# Micro.net
KiCad netlist of a schematic drawn in Altium Designer
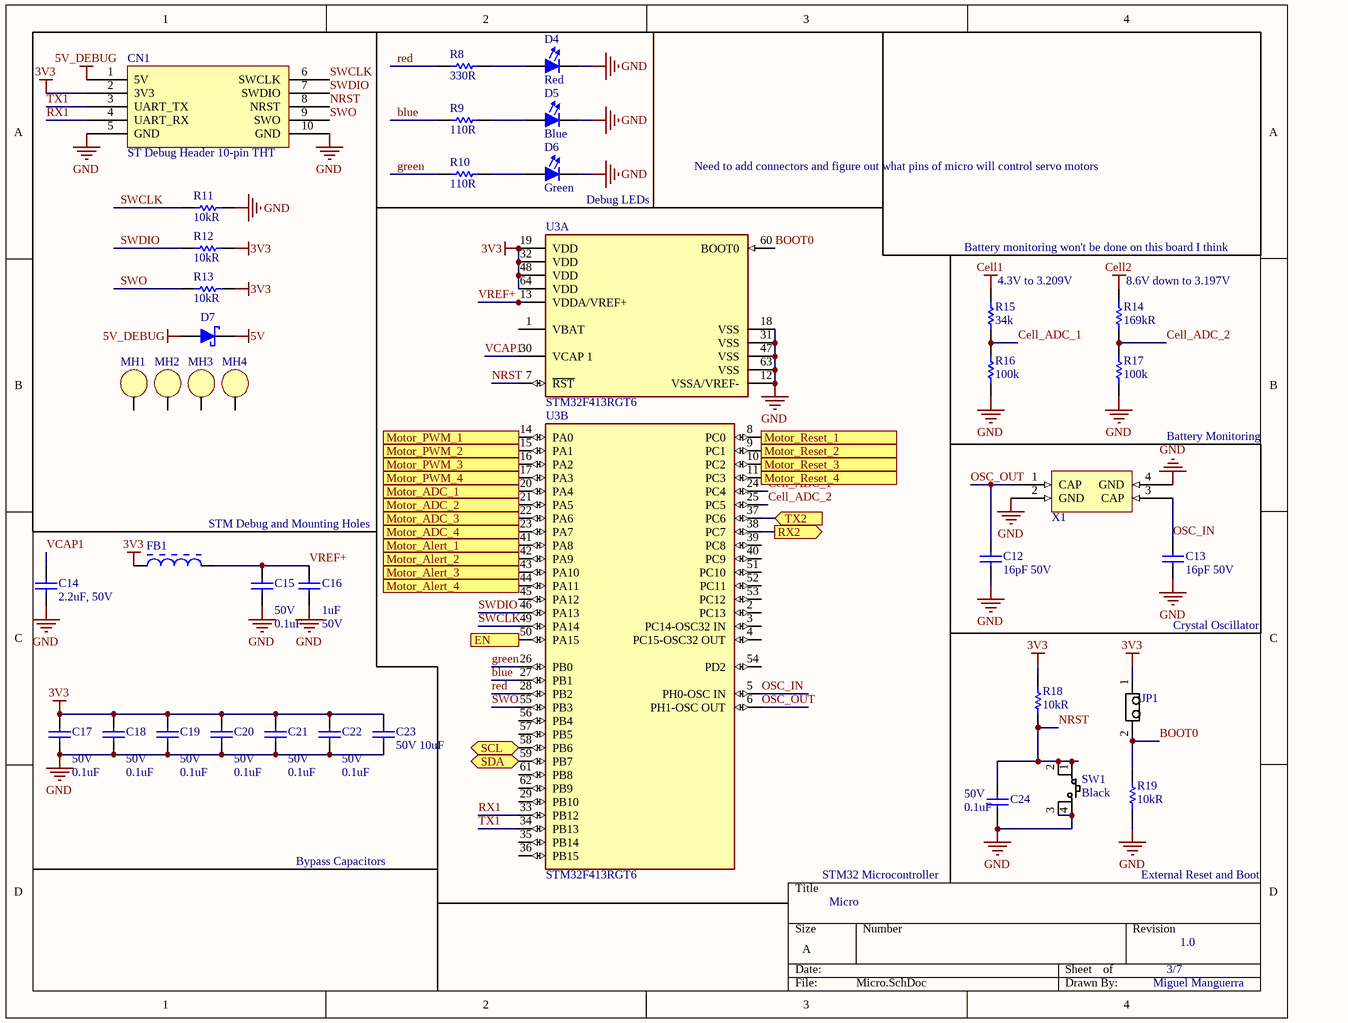
[diagram p0: Micro.SchDoc]

(export (version "E")
  (design (tool "Eeschema 10.0.6"))
  (components
    (comp (ref "C12")
      (value "16pF Ceramic 50V 5% 0603")
      (footprint "CAPC1608X90X35ML10T15")
      (description "Cap Ceramic 16pF 50V C0G 5% SMD 0603 125C Paper T/R")
      (fields (field (name "VOLTAGE") "16pF 50V") (field (name "TOLERANCE") "5%"))
      (libsource (lib "AUVIC") (part "CAP"))
    )
    (comp (ref "C13")
      (value "16pF Ceramic 50V 5% 0603")
      (footprint "CAPC1608X90X35ML10T15")
      (description "Cap Ceramic 16pF 50V C0G 5% SMD 0603 125C Paper T/R")
      (fields (field (name "VOLTAGE") "16pF 50V") (field (name "TOLERANCE") "5%"))
      (libsource (lib "AUVIC") (part "CAP"))
    )
    (comp (ref "C14")
      (value "2.2uF, 50V")
      (footprint "CAPC1608N(0603\")")
      (description "Capacitor, Ceramic, 50V, 10%, 0603 SMD, X5R")
      (fields (field (name "MADE BY") "*") (field (name "PUBLISHER") "AUVic"))
      (libsource (lib "") (part "Symbol_2"))
    )
    (comp (ref "C15")
      (value "CL10B104JB8NNNC")
      (footprint "FP-CL10-0_1-MFG")
      (description "CAP CER 0.1UF 50V X7R 0603")
      (fields
        (field (name "TOLERANCE") "5%")
        (field (name "VOLTAGE") "50V")
        (field (name "CAPACITANCE") "0.1uF")
      )
      (libsource (lib "AUVIC") (part "CAP-NP-2"))
    )
    (comp (ref "C16")
      (value "CL21B105KBFNNNG")
      (footprint "0803 CAP")
      (description "SAMSUNG ELECTRO-MECHANICS - CL21B105KBFNNNG - MLCC CAPACITORS")
      (fields
        (field (name "TOLERANCE") "10%")
        (field (name "CAPACITANCE") "1uF")
        (field (name "VOLTAGE") "50V")
      )
      (libsource (lib "") (part "Symbol_5"))
    )
    (comp (ref "C17")
      (value "CL10B104JB8NNNC")
      (footprint "FP-CL10-0_1-MFG")
      (description "CAP CER 0.1UF 50V X7R 0603")
      (fields
        (field (name "TOLERANCE") "5%")
        (field (name "VOLTAGE") "50V")
        (field (name "CAPACITANCE") "0.1uF")
      )
      (libsource (lib "AUVIC") (part "CAP-NP-2"))
    )
    (comp (ref "C18")
      (value "CL10B104JB8NNNC")
      (footprint "FP-CL10-0_1-MFG")
      (description "CAP CER 0.1UF 50V X7R 0603")
      (fields
        (field (name "TOLERANCE") "5%")
        (field (name "VOLTAGE") "50V")
        (field (name "CAPACITANCE") "0.1uF")
      )
      (libsource (lib "AUVIC") (part "CAP-NP-2"))
    )
    (comp (ref "C19")
      (value "CL10B104JB8NNNC")
      (footprint "FP-CL10-0_1-MFG")
      (description "CAP CER 0.1UF 50V X7R 0603")
      (fields
        (field (name "TOLERANCE") "5%")
        (field (name "VOLTAGE") "50V")
        (field (name "CAPACITANCE") "0.1uF")
      )
      (libsource (lib "AUVIC") (part "CAP-NP-2"))
    )
    (comp (ref "C20")
      (value "CL10B104JB8NNNC")
      (footprint "FP-CL10-0_1-MFG")
      (description "CAP CER 0.1UF 50V X7R 0603")
      (fields
        (field (name "TOLERANCE") "5%")
        (field (name "VOLTAGE") "50V")
        (field (name "CAPACITANCE") "0.1uF")
      )
      (libsource (lib "AUVIC") (part "CAP-NP-2"))
    )
    (comp (ref "C21")
      (value "CL10B104JB8NNNC")
      (footprint "FP-CL10-0_1-MFG")
      (description "CAP CER 0.1UF 50V X7R 0603")
      (fields
        (field (name "TOLERANCE") "5%")
        (field (name "VOLTAGE") "50V")
        (field (name "CAPACITANCE") "0.1uF")
      )
      (libsource (lib "AUVIC") (part "CAP-NP-2"))
    )
    (comp (ref "C22")
      (value "CL10B104JB8NNNC")
      (footprint "FP-CL10-0_1-MFG")
      (description "CAP CER 0.1UF 50V X7R 0603")
      (fields
        (field (name "TOLERANCE") "5%")
        (field (name "VOLTAGE") "50V")
        (field (name "CAPACITANCE") "0.1uF")
      )
      (libsource (lib "AUVIC") (part "CAP-NP-2"))
    )
    (comp (ref "C23")
      (value "50V 10uF")
      (footprint "CAPC3216X180X50LL20T30")
      (description "Cap Ceramic 10uF 50V X7R 10% Pad SMD 1206 125°C T/R")
      (fields (field (name "TOLERANCE") "10%"))
      (libsource (lib "AUVIC") (part "CAP-NP-2"))
    )
    (comp (ref "C24")
      (value "CL10B104JB8NNNC")
      (footprint "FP-CL10-0_1-MFG")
      (description "CAP CER 0.1UF 50V X7R 0603")
      (fields
        (field (name "TOLERANCE") "5%")
        (field (name "VOLTAGE") "50V")
        (field (name "CAPACITANCE") "0.1uF")
      )
      (libsource (lib "AUVIC") (part "CAP-NP-2"))
    )
    (comp (ref "CN1")
      (value "ST Debug Header 10-pin THT")
      (footprint "10-pin shrouded header THT")
      (description "CONN HEADER VERT 10POS 2.54MM")
      (libsource (lib "AUVIC") (part "ST Debug Header 10-pin"))
    )
    (comp (ref "D4")
      (value "Red")
      (footprint "FP-LB_Q39E-MFG")
      (description "LED Red 645nm 2-Pin Chip 0603(1608Metric) T/R")
      (libsource (lib "") (part "Symbol_1"))
    )
    (comp (ref "D5")
      (value "Blue")
      (footprint "FP-LB_Q39E-MFG")
      (description "LED BLUE DIFFUSED 0603 SMD")
      (libsource (lib "") (part "Symbol_1"))
    )
    (comp (ref "D6")
      (value "Green")
      (footprint "FP-LB_Q39E-MFG")
      (description "LED GREEN DIFFUSED 0603 SMD")
      (libsource (lib "") (part "Symbol_1"))
    )
    (comp (ref "D7")
      (value "CUS08F30,H3F")
      (footprint "SC-76")
      (description "Diode Schottky 30V 800mA Surface Mount USC")
      (libsource (lib "") (part "Symbol_4"))
    )
    (comp (ref "FB1")
      (value "BLM18AG601SN1D")
      (footprint "MURA-BLM18-F-H1-CHIP-2_V")
      (fields (field (name "TOLERANCE") "25%"))
      (libsource (lib "AUVIC") (part "MURA-FB-2"))
    )
    (comp (ref "JP1")
      (value "1x2 Male Header")
      (footprint "2X1 Males Header")
      (fields (field (name "MADE BY") "Andy Bates"))
      (libsource (lib "AUVIC") (part "1x2 Male Header"))
    )
    (comp (ref "MH1")
      (value "Mount_Hole_3mm")
      (footprint "Mount-Hole_3mm")
      (description "Mounting hold for M3 hex standoff")
      (libsource (lib "AUVIC") (part "Mount_Hole_3mm"))
    )
    (comp (ref "MH2")
      (value "Mount_Hole_3mm")
      (footprint "Mount-Hole_3mm")
      (description "Mounting hold for M3 hex standoff")
      (libsource (lib "AUVIC") (part "Mount_Hole_3mm"))
    )
    (comp (ref "MH3")
      (value "Mount_Hole_3mm")
      (footprint "Mount-Hole_3mm")
      (description "Mounting hold for M3 hex standoff")
      (libsource (lib "AUVIC") (part "Mount_Hole_3mm"))
    )
    (comp (ref "MH4")
      (value "Mount_Hole_3mm")
      (footprint "Mount-Hole_3mm")
      (description "Mounting hold for M3 hex standoff")
      (libsource (lib "AUVIC") (part "Mount_Hole_3mm"))
    )
    (comp (ref "R8")
      (value "CRCW0603330RFKEA")
      (footprint "FP-CRCW0603-e3-IPC_C")
      (description "Res Thick Film 0603 330 Ohm 1% 0.1W(1/10W) +/-100ppm/ßC Pad SMD Automotive T/R")
      (fields (field (name "TOLERANCE") "1%") (field (name "RESISTANCE") "330R"))
      (libsource (lib "AUVIC") (part "RES"))
    )
    (comp (ref "R9")
      (value "RC0603FR-07110RL")
      (footprint "RESC1608X55X25ML10T15")
      (description "RES SMD 110 OHM 1% 1/10W 0603")
      (fields (field (name "TOLERANCE") "1%") (field (name "RESISTANCE") "110R"))
      (libsource (lib "AUVIC") (part "RES"))
    )
    (comp (ref "R10")
      (value "RC0603FR-07110RL")
      (footprint "RESC1608X55X25ML10T15")
      (description "RES SMD 110 OHM 1% 1/10W 0603")
      (fields (field (name "TOLERANCE") "1%") (field (name "RESISTANCE") "110R"))
      (libsource (lib "AUVIC") (part "RES"))
    )
    (comp (ref "R11")
      (value "10kR")
      (footprint "RESC1608N(0603\")")
      (description "10kR, 1%, 1/10W, 0603 SMD")
      (fields (field (name "MADE BY") "Ashwin Sira"))
      (libsource (lib "AUVIC") (part "Symbol"))
    )
    (comp (ref "R12")
      (value "10kR")
      (footprint "RESC1608N(0603\")")
      (description "10kR, 1%, 1/10W, 0603 SMD")
      (fields (field (name "MADE BY") "Ashwin Sira"))
      (libsource (lib "AUVIC") (part "Symbol"))
    )
    (comp (ref "R13")
      (value "10kR")
      (footprint "RESC1608N(0603\")")
      (description "10kR, 1%, 1/10W, 0603 SMD")
      (fields (field (name "MADE BY") "Ashwin Sira"))
      (libsource (lib "AUVIC") (part "Symbol"))
    )
    (comp (ref "R14")
      (value "169kR, 1%, 1/10W, 0603")
      (footprint "RESC0603(1608)_M")
      (description "RES 169K OHM 1% 1/10W 0603")
      (fields (field (name "RESISTANCE") "169kR") (field (name "TOLERANCE") "1%"))
      (libsource (lib "AUVIC") (part "RES"))
    )
    (comp (ref "R15")
      (value "34kR, 1%, 1/10W, 0603")
      (footprint "RESC1608N(0603\")")
      (description "RES 34K OHM 1/10W 1% 0603 SMD")
      (fields
        (field (name "RESISTANCE") "34k")
        (field (name "MANUFACTURER PART NUMBER") "RC0603FR-0734KL")
        (field (name "MANUFACTURER") "Yageo")
      )
      (libsource (lib "AUVIC") (part "34kR, 1%, 1/10W, 0603"))
    )
    (comp (ref "R16")
      (value "100k")
      (footprint "RESC1608N(0603\")")
      (description "100kR, 1%, 1/10W, 0603 SMD")
      (fields (field (name "MADE BY") "Andy Bates"))
      (libsource (lib "AUVIC") (part "Symbol"))
    )
    (comp (ref "R17")
      (value "100k")
      (footprint "RESC1608N(0603\")")
      (description "100kR, 1%, 1/10W, 0603 SMD")
      (fields (field (name "MADE BY") "Andy Bates"))
      (libsource (lib "AUVIC") (part "Symbol"))
    )
    (comp (ref "R18")
      (value "10kR")
      (footprint "RESC1608N(0603\")")
      (description "10kR, 1%, 1/10W, 0603 SMD")
      (fields (field (name "MADE BY") "Ashwin Sira"))
      (libsource (lib "AUVIC") (part "Symbol"))
    )
    (comp (ref "R19")
      (value "10kR")
      (footprint "RESC1608N(0603\")")
      (description "10kR, 1%, 1/10W, 0603 SMD")
      (fields (field (name "MADE BY") "Ashwin Sira"))
      (libsource (lib "AUVIC") (part "Symbol"))
    )
    (comp (ref "SW1")
      (value "PTS645SL43SMTR92LFS")
      (footprint "4-SPST-NO")
      (description "Black Switch Tactile N.O. SPST Round Button Gull Wing 0.05A 12VDC 100000Cycles 1.27N SMD T/R")
      (fields (field (name "BUTTON COLOUR") "Black"))
      (libsource (lib "") (part "Symbol_3"))
    )
    (comp (ref "U3")
      (value "STM32F413RGT6")
      (footprint "FP-LQFP64-5W-MFG")
      (description "STMICROELECTRONICS - STM32F413RGT6 - MCU, ARM CORTEX-M4, 100MHZ, LQFP-64")
      (libsource (lib "AUVIC") (part "7f3deadac312a1e532344b4e443717e"))
    )
    (comp (ref "X1")
      (value "CRYSTAL 8.0MHZ 16PF SMD")
      (footprint "QFN250P750X520X140_HS-5M")
      (description "8MHz ±30ppm Crystal 16pF 80 Ohms 4-SMD, No Lead")
      (libsource (lib "AUVIC") (part "LFXTAL026380REEL"))
    )
  )
  (nets
    (net (code "1") (name "/BOOT0") (class "Default")
      (node (ref "JP1") (pin "2") (pinfunction "2_2") (pintype "passive"))
      (node (ref "R19") (pin "1") (pinfunction "1_1") (pintype "passive"))
      (node (ref "U3") (pin "60") (pinfunction "BOOT0_60") (pintype "input"))
    )
    (net (code "2") (name "/Cell_ADC_1") (class "Default")
      (node (ref "R15") (pin "1") (pinfunction "1_1") (pintype "passive"))
      (node (ref "R16") (pin "2") (pinfunction "2_2") (pintype "passive"))
      (node (ref "U3") (pin "24") (pinfunction "PC4_24") (pintype "bidirectional"))
    )
    (net (code "3") (name "/Cell_ADC_2") (class "Default")
      (node (ref "R14") (pin "1") (pinfunction "1_1") (pintype "passive"))
      (node (ref "R17") (pin "2") (pinfunction "2_2") (pintype "passive"))
      (node (ref "U3") (pin "25") (pinfunction "PC5_25") (pintype "bidirectional"))
    )
    (net (code "4") (name "/EN") (class "Default")
      (node (ref "U3") (pin "50") (pinfunction "PA15_50") (pintype "bidirectional"))
    )
    (net (code "5") (name "/Motor_ADC_1") (class "Default")
      (node (ref "U3") (pin "20") (pinfunction "PA4_20") (pintype "bidirectional"))
    )
    (net (code "6") (name "/Motor_ADC_2") (class "Default")
      (node (ref "U3") (pin "21") (pinfunction "PA5_21") (pintype "bidirectional"))
    )
    (net (code "7") (name "/Motor_ADC_3") (class "Default")
      (node (ref "U3") (pin "22") (pinfunction "PA6_22") (pintype "bidirectional"))
    )
    (net (code "8") (name "/Motor_ADC_4") (class "Default")
      (node (ref "U3") (pin "23") (pinfunction "PA7_23") (pintype "bidirectional"))
    )
    (net (code "9") (name "/Motor_Alert_1") (class "Default")
      (node (ref "U3") (pin "41") (pinfunction "PA8_41") (pintype "bidirectional"))
    )
    (net (code "10") (name "/Motor_Alert_2") (class "Default")
      (node (ref "U3") (pin "42") (pinfunction "PA9_42") (pintype "bidirectional"))
    )
    (net (code "11") (name "/Motor_Alert_3") (class "Default")
      (node (ref "U3") (pin "43") (pinfunction "PA10_43") (pintype "bidirectional"))
    )
    (net (code "12") (name "/Motor_Alert_4") (class "Default")
      (node (ref "U3") (pin "44") (pinfunction "PA11_44") (pintype "bidirectional"))
    )
    (net (code "13") (name "/Motor_PWM_1") (class "Default")
      (node (ref "U3") (pin "14") (pinfunction "PA0_14") (pintype "bidirectional"))
    )
    (net (code "14") (name "/Motor_PWM_2") (class "Default")
      (node (ref "U3") (pin "15") (pinfunction "PA1_15") (pintype "bidirectional"))
    )
    (net (code "15") (name "/Motor_PWM_3") (class "Default")
      (node (ref "U3") (pin "16") (pinfunction "PA2_16") (pintype "bidirectional"))
    )
    (net (code "16") (name "/Motor_PWM_4") (class "Default")
      (node (ref "U3") (pin "17") (pinfunction "PA3_17") (pintype "bidirectional"))
    )
    (net (code "17") (name "/Motor_Reset_1") (class "Default")
      (node (ref "U3") (pin "8") (pinfunction "PC0_8") (pintype "bidirectional"))
    )
    (net (code "18") (name "/Motor_Reset_2") (class "Default")
      (node (ref "U3") (pin "9") (pinfunction "PC1_9") (pintype "bidirectional"))
    )
    (net (code "19") (name "/Motor_Reset_3") (class "Default")
      (node (ref "U3") (pin "10") (pinfunction "PC2_10") (pintype "bidirectional"))
    )
    (net (code "20") (name "/Motor_Reset_4") (class "Default")
      (node (ref "U3") (pin "11") (pinfunction "PC3_11") (pintype "bidirectional"))
    )
    (net (code "21") (name "/NRST") (class "Default")
      (node (ref "C24") (pin "1") (pinfunction "1_1") (pintype "passive"))
      (node (ref "CN1") (pin "8") (pinfunction "NRST_8") (pintype "passive"))
      (node (ref "R18") (pin "2") (pinfunction "2_2") (pintype "passive"))
      (node (ref "SW1") (pin "1") (pinfunction "1_1") (pintype "passive"))
      (node (ref "SW1") (pin "2") (pinfunction "2_2") (pintype "passive"))
      (node (ref "U3") (pin "7") (pinfunction "~{RST}_7") (pintype "bidirectional"))
    )
    (net (code "22") (name "/OSC_IN") (class "Default")
      (node (ref "C13") (pin "2") (pinfunction "2_2") (pintype "passive"))
      (node (ref "U3") (pin "5") (pinfunction "PH0-OSC_IN_5") (pintype "bidirectional"))
      (node (ref "X1") (pin "3") (pinfunction "CAP_3") (pintype "input"))
    )
    (net (code "23") (name "/OSC_OUT") (class "Default")
      (node (ref "C12") (pin "2") (pinfunction "2_2") (pintype "passive"))
      (node (ref "U3") (pin "6") (pinfunction "PH1-OSC_OUT_6") (pintype "bidirectional"))
      (node (ref "X1") (pin "1") (pinfunction "CAP_1") (pintype "input"))
    )
    (net (code "24") (name "/RX1") (class "Default")
      (node (ref "CN1") (pin "4") (pinfunction "UART_RX_4") (pintype "passive"))
      (node (ref "U3") (pin "33") (pinfunction "PB12_33") (pintype "bidirectional"))
    )
    (net (code "25") (name "/RX2") (class "Default")
      (node (ref "U3") (pin "38") (pinfunction "PC7_38") (pintype "bidirectional"))
    )
    (net (code "26") (name "/SCL") (class "Default")
      (node (ref "U3") (pin "58") (pinfunction "PB6_58") (pintype "bidirectional"))
    )
    (net (code "27") (name "/SDA") (class "Default")
      (node (ref "U3") (pin "59") (pinfunction "PB7_59") (pintype "bidirectional"))
    )
    (net (code "28") (name "/SWCLK") (class "Default")
      (node (ref "CN1") (pin "6") (pinfunction "SWCLK_6") (pintype "passive"))
      (node (ref "R11") (pin "2") (pinfunction "2_2") (pintype "passive"))
      (node (ref "U3") (pin "49") (pinfunction "PA14_49") (pintype "bidirectional"))
    )
    (net (code "29") (name "/SWDIO") (class "Default")
      (node (ref "CN1") (pin "7") (pinfunction "SWDIO_7") (pintype "passive"))
      (node (ref "R12") (pin "2") (pinfunction "2_2") (pintype "passive"))
      (node (ref "U3") (pin "46") (pinfunction "PA13_46") (pintype "bidirectional"))
    )
    (net (code "30") (name "/SWO") (class "Default")
      (node (ref "CN1") (pin "9") (pinfunction "SWO_9") (pintype "passive"))
      (node (ref "R13") (pin "2") (pinfunction "2_2") (pintype "passive"))
      (node (ref "U3") (pin "55") (pinfunction "PB3_55") (pintype "bidirectional"))
    )
    (net (code "31") (name "/TX1") (class "Default")
      (node (ref "CN1") (pin "3") (pinfunction "UART_TX_3") (pintype "passive"))
      (node (ref "U3") (pin "34") (pinfunction "PB13_34") (pintype "bidirectional"))
    )
    (net (code "32") (name "/TX2") (class "Default")
      (node (ref "U3") (pin "37") (pinfunction "PC6_37") (pintype "bidirectional"))
    )
    (net (code "33") (name "/VCAP1") (class "Default")
      (node (ref "C14") (pin "1") (pinfunction "Anode_1") (pintype "passive"))
      (node (ref "U3") (pin "30") (pinfunction "VCAP_1_30") (pintype "power_in"))
    )
    (net (code "34") (name "/VREF+") (class "Default")
      (node (ref "C15") (pin "1") (pinfunction "1_1") (pintype "passive"))
      (node (ref "C16") (pin "1") (pinfunction "1_1") (pintype "passive"))
      (node (ref "FB1") (pin "2") (pinfunction "2_2") (pintype "passive"))
      (node (ref "U3") (pin "13") (pinfunction "VDDA/VREF+_13") (pintype "power_in"))
    )
    (net (code "35") (name "/blue") (class "Default")
      (node (ref "R9") (pin "1") (pinfunction "1_1") (pintype "passive"))
      (node (ref "U3") (pin "27") (pinfunction "PB1_27") (pintype "bidirectional"))
    )
    (net (code "36") (name "/green") (class "Default")
      (node (ref "R10") (pin "1") (pinfunction "1_1") (pintype "passive"))
      (node (ref "U3") (pin "26") (pinfunction "PB0_26") (pintype "bidirectional"))
    )
    (net (code "37") (name "/red") (class "Default")
      (node (ref "R8") (pin "1") (pinfunction "1_1") (pintype "passive"))
      (node (ref "U3") (pin "28") (pinfunction "PB2_28") (pintype "bidirectional"))
    )
    (net (code "38") (name "3V3") (class "Default")
      (node (ref "C17") (pin "1") (pinfunction "1_1") (pintype "passive"))
      (node (ref "C18") (pin "1") (pinfunction "1_1") (pintype "passive"))
      (node (ref "C19") (pin "1") (pinfunction "1_1") (pintype "passive"))
      (node (ref "C20") (pin "1") (pinfunction "1_1") (pintype "passive"))
      (node (ref "C21") (pin "1") (pinfunction "1_1") (pintype "passive"))
      (node (ref "C22") (pin "1") (pinfunction "1_1") (pintype "passive"))
      (node (ref "C23") (pin "1") (pinfunction "1_1") (pintype "passive"))
      (node (ref "CN1") (pin "2") (pinfunction "3V3_2") (pintype "passive"))
      (node (ref "FB1") (pin "1") (pinfunction "1_1") (pintype "passive"))
      (node (ref "JP1") (pin "1") (pinfunction "1_1") (pintype "passive"))
      (node (ref "R12") (pin "1") (pinfunction "1_1") (pintype "passive"))
      (node (ref "R13") (pin "1") (pinfunction "1_1") (pintype "passive"))
      (node (ref "R18") (pin "1") (pinfunction "1_1") (pintype "passive"))
      (node (ref "U3") (pin "19") (pinfunction "VDD_19") (pintype "power_in"))
      (node (ref "U3") (pin "32") (pinfunction "VDD_32") (pintype "power_in"))
      (node (ref "U3") (pin "48") (pinfunction "VDD_48") (pintype "power_in"))
      (node (ref "U3") (pin "64") (pinfunction "VDD_64") (pintype "power_in"))
    )
    (net (code "39") (name "5V") (class "Default")
      (node (ref "D7") (pin "K") (pinfunction "Cathode_K") (pintype "passive"))
    )
    (net (code "40") (name "5V_DEBUG") (class "Default")
      (node (ref "CN1") (pin "1") (pinfunction "5V_1") (pintype "passive"))
      (node (ref "D7") (pin "A") (pinfunction "Anode_A") (pintype "passive"))
    )
    (net (code "41") (name "Cell1") (class "Default")
      (node (ref "R15") (pin "2") (pinfunction "2_2") (pintype "passive"))
    )
    (net (code "42") (name "Cell2") (class "Default")
      (node (ref "R14") (pin "2") (pinfunction "2_2") (pintype "passive"))
    )
    (net (code "43") (name "GND") (class "Default")
      (node (ref "C12") (pin "1") (pinfunction "1_1") (pintype "passive"))
      (node (ref "C13") (pin "1") (pinfunction "1_1") (pintype "passive"))
      (node (ref "C14") (pin "2") (pinfunction "Cathode_2") (pintype "passive"))
      (node (ref "C15") (pin "2") (pinfunction "2_2") (pintype "passive"))
      (node (ref "C16") (pin "2") (pinfunction "2_2") (pintype "passive"))
      (node (ref "C17") (pin "2") (pinfunction "2_2") (pintype "passive"))
      (node (ref "C18") (pin "2") (pinfunction "2_2") (pintype "passive"))
      (node (ref "C19") (pin "2") (pinfunction "2_2") (pintype "passive"))
      (node (ref "C20") (pin "2") (pinfunction "2_2") (pintype "passive"))
      (node (ref "C21") (pin "2") (pinfunction "2_2") (pintype "passive"))
      (node (ref "C22") (pin "2") (pinfunction "2_2") (pintype "passive"))
      (node (ref "C23") (pin "2") (pinfunction "2_2") (pintype "passive"))
      (node (ref "C24") (pin "2") (pinfunction "2_2") (pintype "passive"))
      (node (ref "CN1") (pin "10") (pinfunction "GND_10") (pintype "passive"))
      (node (ref "CN1") (pin "5") (pinfunction "GND_5") (pintype "passive"))
      (node (ref "D4") (pin "1") (pinfunction "Cathode_1") (pintype "passive"))
      (node (ref "D5") (pin "1") (pinfunction "Cathode_1") (pintype "passive"))
      (node (ref "D6") (pin "1") (pinfunction "Cathode_1") (pintype "passive"))
      (node (ref "R11") (pin "1") (pinfunction "1_1") (pintype "passive"))
      (node (ref "R16") (pin "1") (pinfunction "1_1") (pintype "passive"))
      (node (ref "R17") (pin "1") (pinfunction "1_1") (pintype "passive"))
      (node (ref "R19") (pin "2") (pinfunction "2_2") (pintype "passive"))
      (node (ref "SW1") (pin "3") (pinfunction "3_3") (pintype "passive"))
      (node (ref "SW1") (pin "4") (pinfunction "4_4") (pintype "passive"))
      (node (ref "U3") (pin "12") (pinfunction "VSSA/VREF-_12") (pintype "power_in"))
      (node (ref "U3") (pin "18") (pinfunction "VSS_18") (pintype "power_in"))
      (node (ref "U3") (pin "31") (pinfunction "VSS_31") (pintype "power_in"))
      (node (ref "U3") (pin "47") (pinfunction "VSS_47") (pintype "power_in"))
      (node (ref "U3") (pin "63") (pinfunction "VSS_63") (pintype "power_in"))
      (node (ref "X1") (pin "2") (pinfunction "GND_2") (pintype "input"))
      (node (ref "X1") (pin "4") (pinfunction "GND_4") (pintype "input"))
    )
    (net (code "44") (name "Net-(D4-Anode)") (class "Default")
      (node (ref "D4") (pin "2") (pinfunction "Anode_2") (pintype "passive"))
      (node (ref "R8") (pin "2") (pinfunction "2_2") (pintype "passive"))
    )
    (net (code "45") (name "Net-(D5-Anode)") (class "Default")
      (node (ref "D5") (pin "2") (pinfunction "Anode_2") (pintype "passive"))
      (node (ref "R9") (pin "2") (pinfunction "2_2") (pintype "passive"))
    )
    (net (code "46") (name "Net-(D6-Anode)") (class "Default")
      (node (ref "D6") (pin "2") (pinfunction "Anode_2") (pintype "passive"))
      (node (ref "R10") (pin "2") (pinfunction "2_2") (pintype "passive"))
    )
    (net (code "47") (name "unconnected-(MH1-Pad1)") (class "Default")
      (node (ref "MH1") (pin "1") (pinfunction "1_1") (pintype "passive"))
    )
    (net (code "48") (name "unconnected-(MH2-Pad1)") (class "Default")
      (node (ref "MH2") (pin "1") (pinfunction "1_1") (pintype "passive"))
    )
    (net (code "49") (name "unconnected-(MH3-Pad1)") (class "Default")
      (node (ref "MH3") (pin "1") (pinfunction "1_1") (pintype "passive"))
    )
    (net (code "50") (name "unconnected-(MH4-Pad1)") (class "Default")
      (node (ref "MH4") (pin "1") (pinfunction "1_1") (pintype "passive"))
    )
    (net (code "51") (name "unconnected-(U3A-VBAT-Pad1)") (class "Default")
      (node (ref "U3") (pin "1") (pinfunction "VBAT_1") (pintype "power_in"))
    )
    (net (code "52") (name "unconnected-(U3B-PA12-Pad45)") (class "Default")
      (node (ref "U3") (pin "45") (pinfunction "PA12_45") (pintype "bidirectional"))
    )
    (net (code "53") (name "unconnected-(U3B-PB4-Pad56)") (class "Default")
      (node (ref "U3") (pin "56") (pinfunction "PB4_56") (pintype "bidirectional"))
    )
    (net (code "54") (name "unconnected-(U3B-PB5-Pad57)") (class "Default")
      (node (ref "U3") (pin "57") (pinfunction "PB5_57") (pintype "bidirectional"))
    )
    (net (code "55") (name "unconnected-(U3B-PB8-Pad61)") (class "Default")
      (node (ref "U3") (pin "61") (pinfunction "PB8_61") (pintype "bidirectional"))
    )
    (net (code "56") (name "unconnected-(U3B-PB9-Pad62)") (class "Default")
      (node (ref "U3") (pin "62") (pinfunction "PB9_62") (pintype "bidirectional"))
    )
    (net (code "57") (name "unconnected-(U3B-PB10-Pad29)") (class "Default")
      (node (ref "U3") (pin "29") (pinfunction "PB10_29") (pintype "bidirectional"))
    )
    (net (code "58") (name "unconnected-(U3B-PB14-Pad35)") (class "Default")
      (node (ref "U3") (pin "35") (pinfunction "PB14_35") (pintype "bidirectional"))
    )
    (net (code "59") (name "unconnected-(U3B-PB15-Pad36)") (class "Default")
      (node (ref "U3") (pin "36") (pinfunction "PB15_36") (pintype "bidirectional"))
    )
    (net (code "60") (name "unconnected-(U3B-PC8-Pad39)") (class "Default")
      (node (ref "U3") (pin "39") (pinfunction "PC8_39") (pintype "bidirectional"))
    )
    (net (code "61") (name "unconnected-(U3B-PC9-Pad40)") (class "Default")
      (node (ref "U3") (pin "40") (pinfunction "PC9_40") (pintype "bidirectional"))
    )
    (net (code "62") (name "unconnected-(U3B-PC10-Pad51)") (class "Default")
      (node (ref "U3") (pin "51") (pinfunction "PC10_51") (pintype "bidirectional"))
    )
    (net (code "63") (name "unconnected-(U3B-PC11-Pad52)") (class "Default")
      (node (ref "U3") (pin "52") (pinfunction "PC11_52") (pintype "bidirectional"))
    )
    (net (code "64") (name "unconnected-(U3B-PC12-Pad53)") (class "Default")
      (node (ref "U3") (pin "53") (pinfunction "PC12_53") (pintype "bidirectional"))
    )
    (net (code "65") (name "unconnected-(U3B-PC13-Pad2)") (class "Default")
      (node (ref "U3") (pin "2") (pinfunction "PC13_2") (pintype "bidirectional"))
    )
    (net (code "66") (name "unconnected-(U3B-PC14-OSC32_IN-Pad3)") (class "Default")
      (node (ref "U3") (pin "3") (pinfunction "PC14-OSC32_IN_3") (pintype "bidirectional"))
    )
    (net (code "67") (name "unconnected-(U3B-PC15-OSC32_OUT-Pad4)") (class "Default")
      (node (ref "U3") (pin "4") (pinfunction "PC15-OSC32_OUT_4") (pintype "bidirectional"))
    )
    (net (code "68") (name "unconnected-(U3B-PD2-Pad54)") (class "Default")
      (node (ref "U3") (pin "54") (pinfunction "PD2_54") (pintype "bidirectional"))
    )
  )
)
